# lighting_circuit.net
KiCad netlist of a schematic drawn in EAGLE
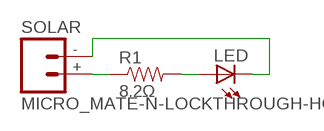
[diagram p0: schematic, sheet 1]

(export (version "E")
  (design (tool "Eeschema 10.0.6"))
  (components
    (comp (ref "LED")
      (value "LED")
      (footprint "eagle-import:PLCC6")
      (libsource (lib "eagle-import") (part "LED"))
    )
    (comp (ref "R1")
      (value "8.2Ω")
      (footprint "eagle-import:1206")
      (libsource (lib "eagle-import") (part "RESISTOR1206"))
    )
    (comp (ref "SOLAR")
      (value "MICRO_MATE-N-LOCKTHROUGH-HOLE")
      (footprint "eagle-import:2-1445093-2")
      (libsource (lib "eagle-import") (part "MICRO_MATE-N-LOCKTHROUGH-HOLE"))
    )
  )
  (nets
    (net (code "1") (name "Net-(LED-A-Pad1)") (class "Default")
      (node (ref "LED") (pin "1") (pinfunction "A_1") (pintype "passive"))
      (node (ref "LED") (pin "2") (pinfunction "A_2") (pintype "passive"))
      (node (ref "LED") (pin "3") (pinfunction "A_3") (pintype "passive"))
      (node (ref "R1") (pin "2") (pinfunction "2_2") (pintype "passive"))
    )
    (net (code "2") (name "Net-(SOLAR-1)") (class "Default")
      (node (ref "R1") (pin "1") (pinfunction "1_1") (pintype "passive"))
      (node (ref "SOLAR") (pin "+") (pinfunction "1_+") (pintype "passive"))
    )
    (net (code "3") (name "Net-(SOLAR-2)") (class "Default")
      (node (ref "LED") (pin "4") (pinfunction "C_4") (pintype "passive"))
      (node (ref "LED") (pin "5") (pinfunction "C_5") (pintype "passive"))
      (node (ref "LED") (pin "6") (pinfunction "C_6") (pintype "passive"))
      (node (ref "SOLAR") (pin "-") (pinfunction "2_-") (pintype "passive"))
    )
  )
)
